# powerSupply.net
KiCad netlist of a schematic drawn in EAGLE
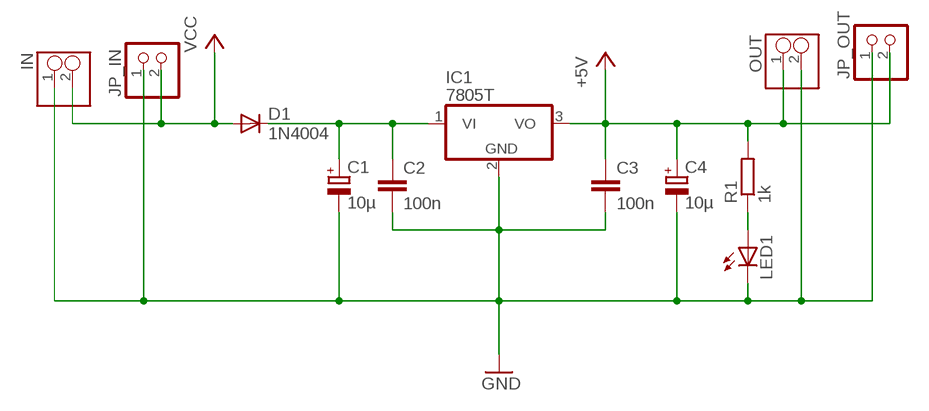
[diagram p0: schematic, sheet 1]

(export (version "E")
  (design (tool "Eeschema 10.0.6"))
  (components
    (comp (ref "C1")
      (value "10µ")
      (footprint "eagle-import:E2,5-6")
      (libsource (lib "eagle-import") (part "CPOL-EUE2.5-6"))
    )
    (comp (ref "C2")
      (value "100n")
      (footprint "eagle-import:C025-024X044")
      (libsource (lib "eagle-import") (part "C-EU025-024X044"))
    )
    (comp (ref "C3")
      (value "100n")
      (footprint "eagle-import:C025-024X044")
      (libsource (lib "eagle-import") (part "C-EU025-024X044"))
    )
    (comp (ref "C4")
      (value "10µ")
      (footprint "eagle-import:E2,5-6")
      (libsource (lib "eagle-import") (part "CPOL-EUE2.5-6"))
    )
    (comp (ref "D1")
      (value "1N4004")
      (footprint "eagle-import:DO41-10")
      (libsource (lib "eagle-import") (part "1N4004"))
    )
    (comp (ref "IC1")
      (value "7805T")
      (footprint "eagle-import:TO220H")
      (libsource (lib "eagle-import") (part "78T05"))
    )
    (comp (ref "IN")
      (value "GENERIC-1X2_PINWAGO-5MM")
      (footprint "eagle-import:WAGO-5MM-2_PIN")
      (libsource (lib "eagle-import") (part "GENERIC-1X2_PINWAGO-5MM"))
    )
    (comp (ref "JP_IN")
      (value "PINHD-1X2")
      (footprint "eagle-import:1X02")
      (libsource (lib "eagle-import") (part "PINHD-1X2"))
    )
    (comp (ref "JP_OUT")
      (value "PINHD-1X2")
      (footprint "eagle-import:1X02")
      (libsource (lib "eagle-import") (part "PINHD-1X2"))
    )
    (comp (ref "LED1")
      (value "LED3MM")
      (footprint "eagle-import:LED3MM")
      (libsource (lib "eagle-import") (part "LED3MM"))
    )
    (comp (ref "OUT")
      (value "GENERIC-1X2_PINWAGO-5MM")
      (footprint "eagle-import:WAGO-5MM-2_PIN")
      (libsource (lib "eagle-import") (part "GENERIC-1X2_PINWAGO-5MM"))
    )
    (comp (ref "R1")
      (value "1k")
      (footprint "eagle-import:0207_7")
      (libsource (lib "eagle-import") (part "R-EU_0207/7"))
    )
  )
  (nets
    (net (code "1") (name "+5V") (class "Default")
      (node (ref "C3") (pin "1") (pinfunction "1_1") (pintype "passive"))
      (node (ref "C4") (pin "+") (pinfunction "+_+") (pintype "passive"))
      (node (ref "IC1") (pin "3") (pinfunction "VO_3") (pintype "passive"))
      (node (ref "JP_OUT") (pin "2") (pinfunction "2_2") (pintype "passive"))
      (node (ref "OUT") (pin "1") (pinfunction "1_1") (pintype "bidirectional"))
      (node (ref "R1") (pin "2") (pinfunction "2_2") (pintype "passive"))
    )
    (net (code "2") (name "GND") (class "Default")
      (node (ref "C1") (pin "-") (pinfunction "-_-") (pintype "passive"))
      (node (ref "C2") (pin "2") (pinfunction "2_2") (pintype "passive"))
      (node (ref "C3") (pin "2") (pinfunction "2_2") (pintype "passive"))
      (node (ref "C4") (pin "-") (pinfunction "-_-") (pintype "passive"))
      (node (ref "IC1") (pin "2") (pinfunction "GND_2") (pintype "passive"))
      (node (ref "IN") (pin "1") (pinfunction "1_1") (pintype "bidirectional"))
      (node (ref "JP_IN") (pin "1") (pinfunction "1_1") (pintype "passive"))
      (node (ref "JP_OUT") (pin "1") (pinfunction "1_1") (pintype "passive"))
      (node (ref "LED1") (pin "K") (pinfunction "C_K") (pintype "passive"))
      (node (ref "OUT") (pin "2") (pinfunction "2_2") (pintype "bidirectional"))
    )
    (net (code "3") (name "Net-(IC1-VI)") (class "Default")
      (node (ref "C1") (pin "+") (pinfunction "+_+") (pintype "passive"))
      (node (ref "C2") (pin "1") (pinfunction "1_1") (pintype "passive"))
      (node (ref "D1") (pin "C") (pinfunction "C_C") (pintype "passive"))
      (node (ref "IC1") (pin "1") (pinfunction "VI_1") (pintype "input"))
    )
    (net (code "4") (name "Net-(LED1-PadA)") (class "Default")
      (node (ref "LED1") (pin "A") (pinfunction "A_A") (pintype "passive"))
      (node (ref "R1") (pin "1") (pinfunction "1_1") (pintype "passive"))
    )
    (net (code "5") (name "VCC") (class "Default")
      (node (ref "D1") (pin "A") (pinfunction "A_A") (pintype "passive"))
      (node (ref "IN") (pin "2") (pinfunction "2_2") (pintype "bidirectional"))
      (node (ref "JP_IN") (pin "2") (pinfunction "2_2") (pintype "passive"))
    )
  )
)
